# P_09__eMMC_QSPI.net
KiCad netlist of a schematic drawn in Altium Designer
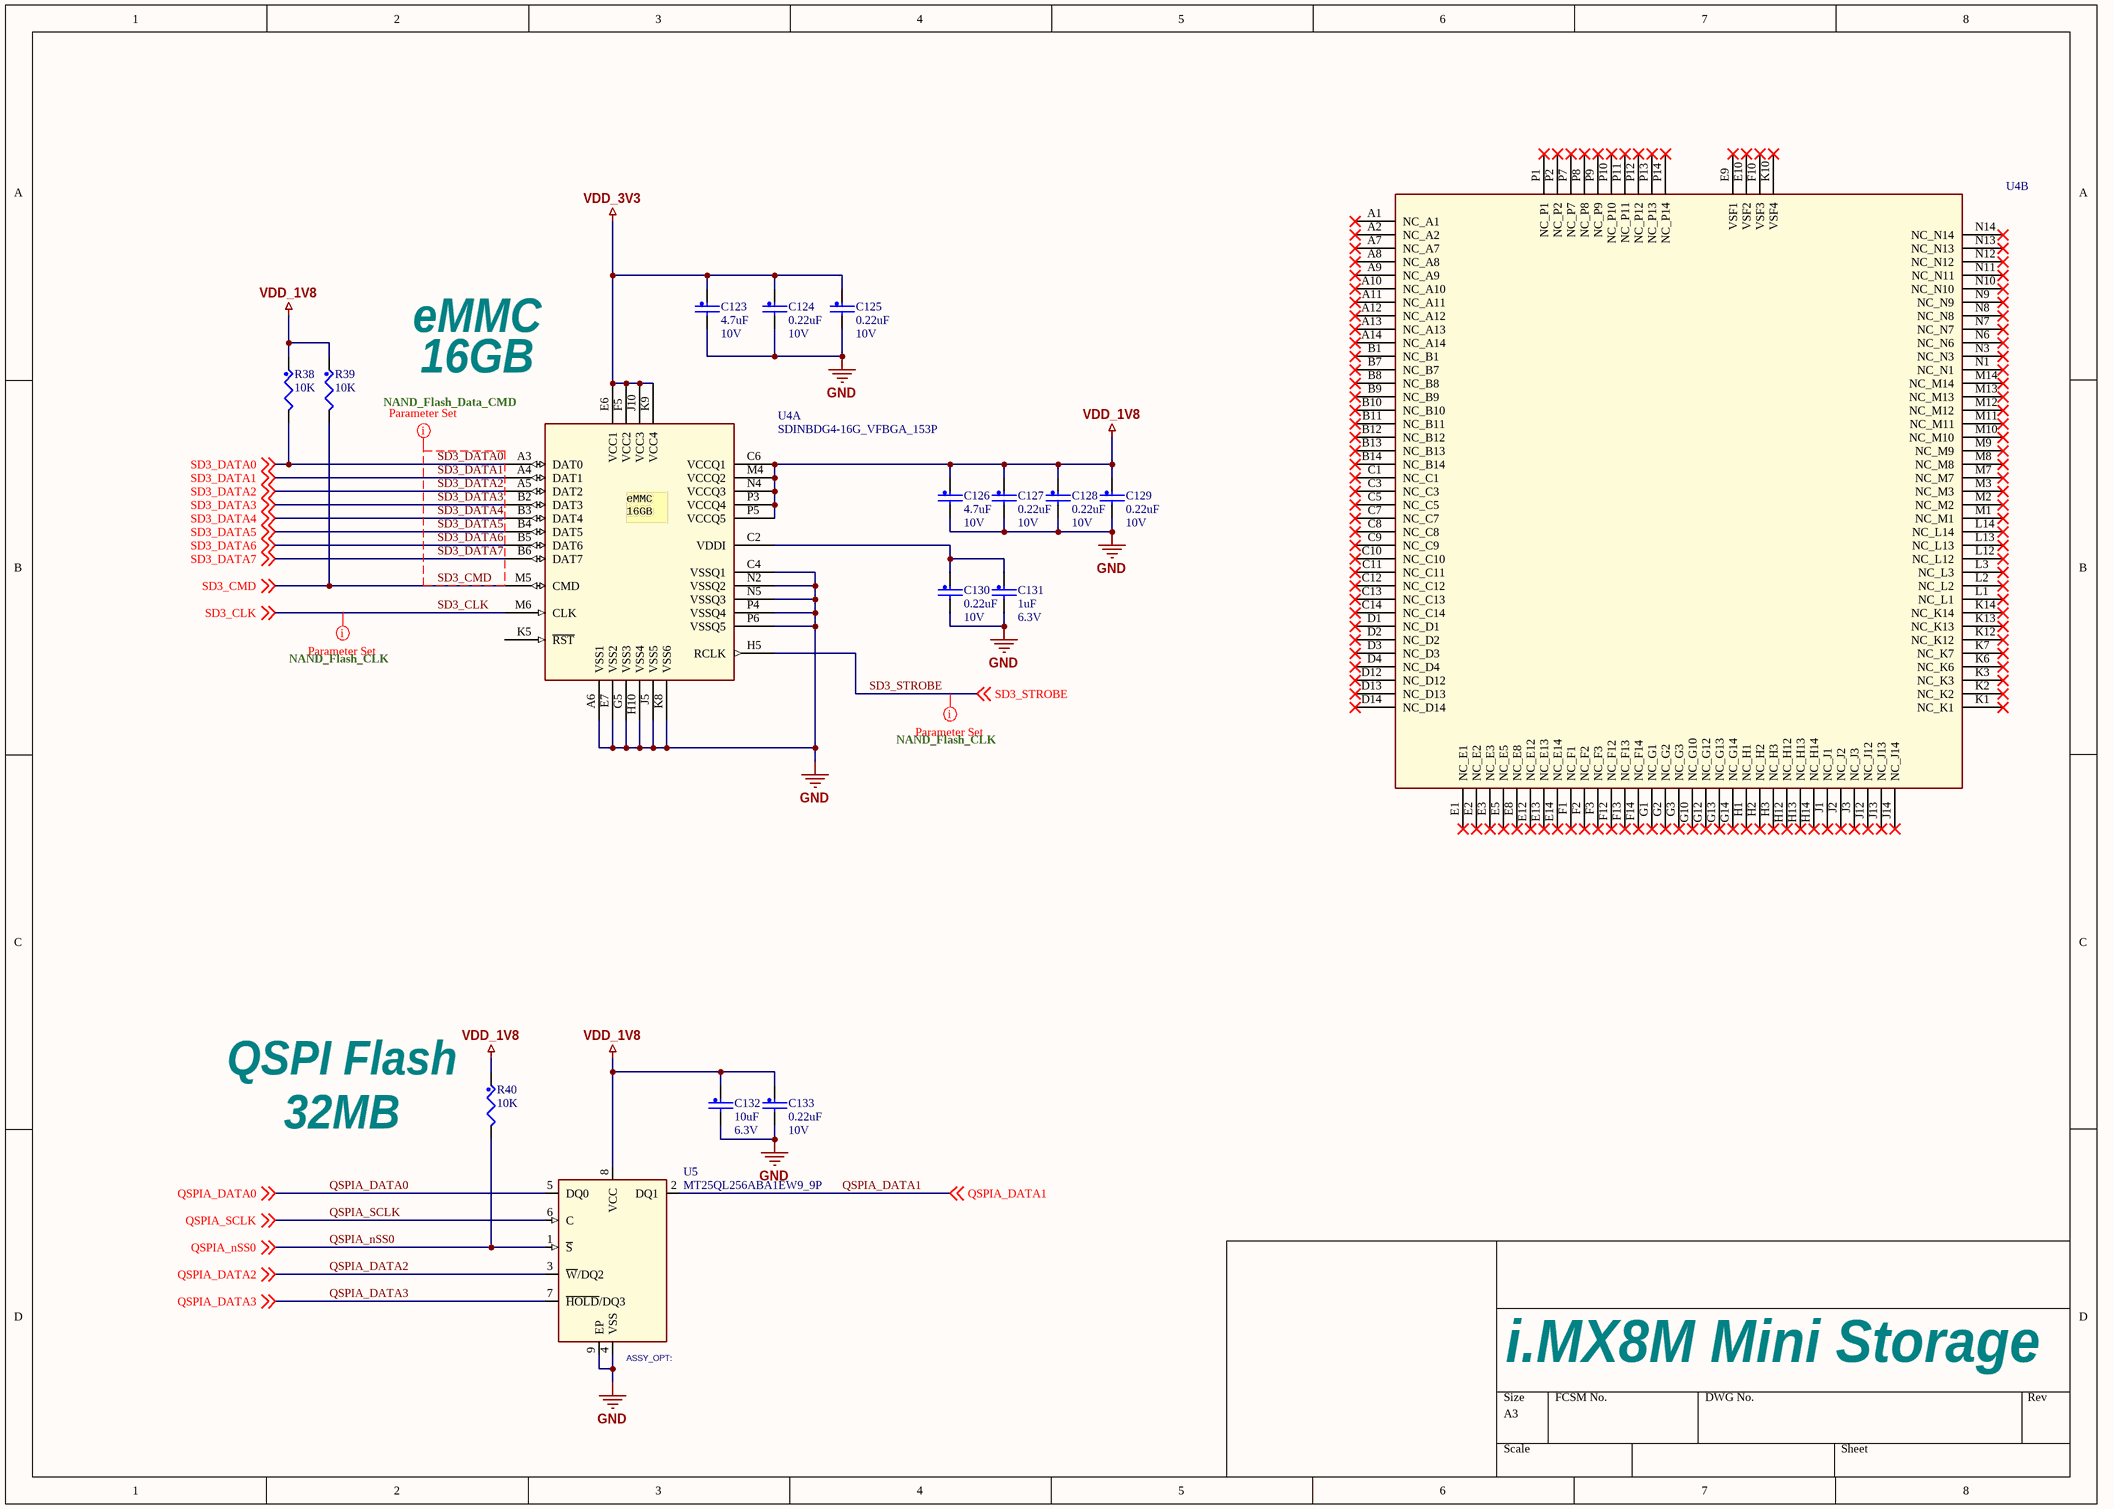
[diagram p0: P[09]_eMMC_QSPI.SchDoc]

(export (version "E")
  (design (tool "Eeschema 10.0.6"))
  (components
    (comp (ref "C123")
      (value "4.7uF")
      (footprint "0402_CC - C")
      (fields (field (name "VOLTAGE") "10V"))
      (libsource (lib "AA_iMX8_M_") (part "CAP_NP"))
    )
    (comp (ref "C124")
      (value "0.22uF")
      (footprint "0201_CC - C")
      (fields (field (name "VOLTAGE") "10V"))
      (libsource (lib "AA_iMX8_M_") (part "CAP_NP"))
    )
    (comp (ref "C125")
      (value "0.22uF")
      (footprint "0201_CC - C")
      (fields (field (name "VOLTAGE") "10V"))
      (libsource (lib "AA_iMX8_M_") (part "CAP_NP"))
    )
    (comp (ref "C126")
      (value "4.7uF")
      (footprint "0402_CC - C")
      (fields (field (name "VOLTAGE") "10V"))
      (libsource (lib "AA_iMX8_M_") (part "CAP_NP"))
    )
    (comp (ref "C127")
      (value "0.22uF")
      (footprint "0201_CC - C")
      (fields (field (name "VOLTAGE") "10V"))
      (libsource (lib "AA_iMX8_M_") (part "CAP_NP"))
    )
    (comp (ref "C128")
      (value "0.22uF")
      (footprint "0201_CC - C")
      (fields (field (name "VOLTAGE") "10V"))
      (libsource (lib "AA_iMX8_M_") (part "CAP_NP"))
    )
    (comp (ref "C129")
      (value "0.22uF")
      (footprint "0201_CC - C")
      (fields (field (name "VOLTAGE") "10V"))
      (libsource (lib "AA_iMX8_M_") (part "CAP_NP"))
    )
    (comp (ref "C130")
      (value "0.22uF")
      (footprint "0201_CC - C")
      (fields (field (name "VOLTAGE") "10V"))
      (libsource (lib "AA_iMX8_M_") (part "CAP_NP"))
    )
    (comp (ref "C131")
      (value "1uF")
      (footprint "0201_CC - C")
      (fields (field (name "VOLTAGE") "6.3V"))
      (libsource (lib "AA_iMX8_M_") (part "CAP_NP"))
    )
    (comp (ref "C132")
      (value "10uF")
      (footprint "0402_CC - C")
      (fields (field (name "VOLTAGE") "6.3V"))
      (libsource (lib "AA_iMX8_M_") (part "CAP_NP"))
    )
    (comp (ref "C133")
      (value "0.22uF")
      (footprint "0201_CC - C")
      (fields (field (name "VOLTAGE") "10V"))
      (libsource (lib "AA_iMX8_M_") (part "CAP_NP"))
    )
    (comp (ref "R38") (value "10K") (footprint "0201_CC") (libsource (lib "AA_iMX8_M_") (part "RES")))
    (comp (ref "R39") (value "10K") (footprint "0201_CC") (libsource (lib "AA_iMX8_M_") (part "RES")))
    (comp (ref "R40") (value "10K") (footprint "0402_CC") (libsource (lib "AA_iMX8_M_") (part "RES")))
    (comp (ref "U4")
      (value "SDINBDG4-16G_VFBGA_153P")
      (footprint "FBGA153_0P5_11P5X13")
      (libsource (lib "AA_iMX8_M_") (part "SDINBDG4-16G_VFBGA_153P"))
    )
    (comp (ref "U5")
      (value "MT25QL256ABA1EW9_9P")
      (footprint "DFN8_1P27_6X5MM_3P1")
      (libsource (lib "AA_iMX8_M_") (part "MT25QL256ABA1EW9_9P"))
    )
  )
  (nets
    (net (code "1") (name "GND") (class "Default")
      (node (ref "C123") (pin "2") (pinfunction "2_2") (pintype "passive"))
      (node (ref "C124") (pin "2") (pinfunction "2_2") (pintype "passive"))
      (node (ref "C125") (pin "2") (pinfunction "2_2") (pintype "passive"))
      (node (ref "C126") (pin "2") (pinfunction "2_2") (pintype "passive"))
      (node (ref "C127") (pin "2") (pinfunction "2_2") (pintype "passive"))
      (node (ref "C128") (pin "2") (pinfunction "2_2") (pintype "passive"))
      (node (ref "C129") (pin "2") (pinfunction "2_2") (pintype "passive"))
      (node (ref "C130") (pin "2") (pinfunction "2_2") (pintype "passive"))
      (node (ref "C131") (pin "2") (pinfunction "2_2") (pintype "passive"))
      (node (ref "C132") (pin "2") (pinfunction "2_2") (pintype "passive"))
      (node (ref "C133") (pin "2") (pinfunction "2_2") (pintype "passive"))
      (node (ref "U4") (pin "A6") (pinfunction "VSS1_A6") (pintype "power_in"))
      (node (ref "U4") (pin "C4") (pinfunction "VSSQ1_C4") (pintype "power_in"))
      (node (ref "U4") (pin "E7") (pinfunction "VSS2_E7") (pintype "power_in"))
      (node (ref "U4") (pin "G5") (pinfunction "VSS3_G5") (pintype "power_in"))
      (node (ref "U4") (pin "H10") (pinfunction "VSS4_H10") (pintype "power_in"))
      (node (ref "U4") (pin "J5") (pinfunction "VSS5_J5") (pintype "power_in"))
      (node (ref "U4") (pin "K8") (pinfunction "VSS6_K8") (pintype "power_in"))
      (node (ref "U4") (pin "N2") (pinfunction "VSSQ2_N2") (pintype "power_in"))
      (node (ref "U4") (pin "N5") (pinfunction "VSSQ3_N5") (pintype "power_in"))
      (node (ref "U4") (pin "P4") (pinfunction "VSSQ4_P4") (pintype "power_in"))
      (node (ref "U4") (pin "P6") (pinfunction "VSSQ5_P6") (pintype "power_in"))
      (node (ref "U5") (pin "4") (pinfunction "VSS_4") (pintype "power_in"))
      (node (ref "U5") (pin "9") (pinfunction "EP_9") (pintype "power_in"))
    )
    (net (code "2") (name "Net-(U4A-VDDI)") (class "Default")
      (node (ref "C130") (pin "1") (pinfunction "1_1") (pintype "passive"))
      (node (ref "C131") (pin "1") (pinfunction "1_1") (pintype "passive"))
      (node (ref "U4") (pin "C2") (pinfunction "VDDI_C2") (pintype "power_in"))
    )
    (net (code "3") (name "QSPIA_DATA0") (class "Default")
      (node (ref "U5") (pin "5") (pinfunction "DQ0_5") (pintype "bidirectional"))
    )
    (net (code "4") (name "QSPIA_DATA1") (class "Default")
      (node (ref "U5") (pin "2") (pinfunction "DQ1_2") (pintype "bidirectional"))
    )
    (net (code "5") (name "QSPIA_DATA2") (class "Default")
      (node (ref "U5") (pin "3") (pinfunction "~{W}/DQ2_3") (pintype "bidirectional"))
    )
    (net (code "6") (name "QSPIA_DATA3") (class "Default")
      (node (ref "U5") (pin "7") (pinfunction "~{HOLD}/DQ3_7") (pintype "bidirectional"))
    )
    (net (code "7") (name "QSPIA_SCLK") (class "Default")
      (node (ref "U5") (pin "6") (pinfunction "C_6") (pintype "input"))
    )
    (net (code "8") (name "QSPIA_nSS0") (class "Default")
      (node (ref "R40") (pin "2") (pinfunction "2_2") (pintype "passive"))
      (node (ref "U5") (pin "1") (pinfunction "~{S}_1") (pintype "input"))
    )
    (net (code "9") (name "SD3_CLK") (class "Default")
      (node (ref "U4") (pin "M6") (pinfunction "CLK_M6") (pintype "input"))
    )
    (net (code "10") (name "SD3_CMD") (class "Default")
      (node (ref "R39") (pin "2") (pinfunction "2_2") (pintype "passive"))
      (node (ref "U4") (pin "M5") (pinfunction "CMD_M5") (pintype "bidirectional"))
    )
    (net (code "11") (name "SD3_DATA0") (class "Default")
      (node (ref "R38") (pin "2") (pinfunction "2_2") (pintype "passive"))
      (node (ref "U4") (pin "A3") (pinfunction "DAT0_A3") (pintype "bidirectional"))
    )
    (net (code "12") (name "SD3_DATA1") (class "Default")
      (node (ref "U4") (pin "A4") (pinfunction "DAT1_A4") (pintype "bidirectional"))
    )
    (net (code "13") (name "SD3_DATA2") (class "Default")
      (node (ref "U4") (pin "A5") (pinfunction "DAT2_A5") (pintype "bidirectional"))
    )
    (net (code "14") (name "SD3_DATA3") (class "Default")
      (node (ref "U4") (pin "B2") (pinfunction "DAT3_B2") (pintype "bidirectional"))
    )
    (net (code "15") (name "SD3_DATA4") (class "Default")
      (node (ref "U4") (pin "B3") (pinfunction "DAT4_B3") (pintype "bidirectional"))
    )
    (net (code "16") (name "SD3_DATA5") (class "Default")
      (node (ref "U4") (pin "B4") (pinfunction "DAT5_B4") (pintype "bidirectional"))
    )
    (net (code "17") (name "SD3_DATA6") (class "Default")
      (node (ref "U4") (pin "B5") (pinfunction "DAT6_B5") (pintype "bidirectional"))
    )
    (net (code "18") (name "SD3_DATA7") (class "Default")
      (node (ref "U4") (pin "B6") (pinfunction "DAT7_B6") (pintype "bidirectional"))
    )
    (net (code "19") (name "SD3_STROBE") (class "Default")
      (node (ref "U4") (pin "H5") (pinfunction "RCLK_H5") (pintype "output"))
    )
    (net (code "20") (name "VDD_1V8") (class "Default")
      (node (ref "C126") (pin "1") (pinfunction "1_1") (pintype "passive"))
      (node (ref "C127") (pin "1") (pinfunction "1_1") (pintype "passive"))
      (node (ref "C128") (pin "1") (pinfunction "1_1") (pintype "passive"))
      (node (ref "C129") (pin "1") (pinfunction "1_1") (pintype "passive"))
      (node (ref "C132") (pin "1") (pinfunction "1_1") (pintype "passive"))
      (node (ref "C133") (pin "1") (pinfunction "1_1") (pintype "passive"))
      (node (ref "R38") (pin "1") (pinfunction "1_1") (pintype "passive"))
      (node (ref "R39") (pin "1") (pinfunction "1_1") (pintype "passive"))
      (node (ref "R40") (pin "1") (pinfunction "1_1") (pintype "passive"))
      (node (ref "U4") (pin "C6") (pinfunction "VCCQ1_C6") (pintype "power_in"))
      (node (ref "U4") (pin "M4") (pinfunction "VCCQ2_M4") (pintype "power_in"))
      (node (ref "U4") (pin "N4") (pinfunction "VCCQ3_N4") (pintype "power_in"))
      (node (ref "U4") (pin "P3") (pinfunction "VCCQ4_P3") (pintype "power_in"))
      (node (ref "U4") (pin "P5") (pinfunction "VCCQ5_P5") (pintype "power_in"))
      (node (ref "U5") (pin "8") (pinfunction "VCC_8") (pintype "power_in"))
    )
    (net (code "21") (name "VDD_3V3") (class "Default")
      (node (ref "C123") (pin "1") (pinfunction "1_1") (pintype "passive"))
      (node (ref "C124") (pin "1") (pinfunction "1_1") (pintype "passive"))
      (node (ref "C125") (pin "1") (pinfunction "1_1") (pintype "passive"))
      (node (ref "U4") (pin "E6") (pinfunction "VCC1_E6") (pintype "power_in"))
      (node (ref "U4") (pin "F5") (pinfunction "VCC2_F5") (pintype "power_in"))
      (node (ref "U4") (pin "J10") (pinfunction "VCC3_J10") (pintype "power_in"))
      (node (ref "U4") (pin "K9") (pinfunction "VCC4_K9") (pintype "power_in"))
    )
    (net (code "22") (name "unconnected-(U4A-~{RST}-PadK5)") (class "Default")
      (node (ref "U4") (pin "K5") (pinfunction "~{RST}_K5") (pintype "input"))
    )
    (net (code "23") (name "unconnected-(U4B-NC_A1-PadA1)") (class "Default")
      (node (ref "U4") (pin "A1") (pinfunction "NC_A1_A1") (pintype "passive+no_connect"))
    )
    (net (code "24") (name "unconnected-(U4B-NC_A2-PadA2)") (class "Default")
      (node (ref "U4") (pin "A2") (pinfunction "NC_A2_A2") (pintype "passive+no_connect"))
    )
    (net (code "25") (name "unconnected-(U4B-NC_A7-PadA7)") (class "Default")
      (node (ref "U4") (pin "A7") (pinfunction "NC_A7_A7") (pintype "passive+no_connect"))
    )
    (net (code "26") (name "unconnected-(U4B-NC_A8-PadA8)") (class "Default")
      (node (ref "U4") (pin "A8") (pinfunction "NC_A8_A8") (pintype "passive+no_connect"))
    )
    (net (code "27") (name "unconnected-(U4B-NC_A9-PadA9)") (class "Default")
      (node (ref "U4") (pin "A9") (pinfunction "NC_A9_A9") (pintype "passive+no_connect"))
    )
    (net (code "28") (name "unconnected-(U4B-NC_A10-PadA10)") (class "Default")
      (node (ref "U4") (pin "A10") (pinfunction "NC_A10_A10") (pintype "passive+no_connect"))
    )
    (net (code "29") (name "unconnected-(U4B-NC_A11-PadA11)") (class "Default")
      (node (ref "U4") (pin "A11") (pinfunction "NC_A11_A11") (pintype "passive+no_connect"))
    )
    (net (code "30") (name "unconnected-(U4B-NC_A12-PadA12)") (class "Default")
      (node (ref "U4") (pin "A12") (pinfunction "NC_A12_A12") (pintype "passive+no_connect"))
    )
    (net (code "31") (name "unconnected-(U4B-NC_A13-PadA13)") (class "Default")
      (node (ref "U4") (pin "A13") (pinfunction "NC_A13_A13") (pintype "passive+no_connect"))
    )
    (net (code "32") (name "unconnected-(U4B-NC_A14-PadA14)") (class "Default")
      (node (ref "U4") (pin "A14") (pinfunction "NC_A14_A14") (pintype "passive+no_connect"))
    )
    (net (code "33") (name "unconnected-(U4B-NC_B1-PadB1)") (class "Default")
      (node (ref "U4") (pin "B1") (pinfunction "NC_B1_B1") (pintype "passive+no_connect"))
    )
    (net (code "34") (name "unconnected-(U4B-NC_B7-PadB7)") (class "Default")
      (node (ref "U4") (pin "B7") (pinfunction "NC_B7_B7") (pintype "passive+no_connect"))
    )
    (net (code "35") (name "unconnected-(U4B-NC_B8-PadB8)") (class "Default")
      (node (ref "U4") (pin "B8") (pinfunction "NC_B8_B8") (pintype "passive+no_connect"))
    )
    (net (code "36") (name "unconnected-(U4B-NC_B9-PadB9)") (class "Default")
      (node (ref "U4") (pin "B9") (pinfunction "NC_B9_B9") (pintype "passive+no_connect"))
    )
    (net (code "37") (name "unconnected-(U4B-NC_B10-PadB10)") (class "Default")
      (node (ref "U4") (pin "B10") (pinfunction "NC_B10_B10") (pintype "passive+no_connect"))
    )
    (net (code "38") (name "unconnected-(U4B-NC_B11-PadB11)") (class "Default")
      (node (ref "U4") (pin "B11") (pinfunction "NC_B11_B11") (pintype "passive+no_connect"))
    )
    (net (code "39") (name "unconnected-(U4B-NC_B12-PadB12)") (class "Default")
      (node (ref "U4") (pin "B12") (pinfunction "NC_B12_B12") (pintype "passive+no_connect"))
    )
    (net (code "40") (name "unconnected-(U4B-NC_B13-PadB13)") (class "Default")
      (node (ref "U4") (pin "B13") (pinfunction "NC_B13_B13") (pintype "passive+no_connect"))
    )
    (net (code "41") (name "unconnected-(U4B-NC_B14-PadB14)") (class "Default")
      (node (ref "U4") (pin "B14") (pinfunction "NC_B14_B14") (pintype "passive+no_connect"))
    )
    (net (code "42") (name "unconnected-(U4B-NC_C1-PadC1)") (class "Default")
      (node (ref "U4") (pin "C1") (pinfunction "NC_C1_C1") (pintype "passive+no_connect"))
    )
    (net (code "43") (name "unconnected-(U4B-NC_C3-PadC3)") (class "Default")
      (node (ref "U4") (pin "C3") (pinfunction "NC_C3_C3") (pintype "passive+no_connect"))
    )
    (net (code "44") (name "unconnected-(U4B-NC_C5-PadC5)") (class "Default")
      (node (ref "U4") (pin "C5") (pinfunction "NC_C5_C5") (pintype "passive+no_connect"))
    )
    (net (code "45") (name "unconnected-(U4B-NC_C7-PadC7)") (class "Default")
      (node (ref "U4") (pin "C7") (pinfunction "NC_C7_C7") (pintype "passive+no_connect"))
    )
    (net (code "46") (name "unconnected-(U4B-NC_C8-PadC8)") (class "Default")
      (node (ref "U4") (pin "C8") (pinfunction "NC_C8_C8") (pintype "passive+no_connect"))
    )
    (net (code "47") (name "unconnected-(U4B-NC_C9-PadC9)") (class "Default")
      (node (ref "U4") (pin "C9") (pinfunction "NC_C9_C9") (pintype "passive+no_connect"))
    )
    (net (code "48") (name "unconnected-(U4B-NC_C10-PadC10)") (class "Default")
      (node (ref "U4") (pin "C10") (pinfunction "NC_C10_C10") (pintype "passive+no_connect"))
    )
    (net (code "49") (name "unconnected-(U4B-NC_C11-PadC11)") (class "Default")
      (node (ref "U4") (pin "C11") (pinfunction "NC_C11_C11") (pintype "passive+no_connect"))
    )
    (net (code "50") (name "unconnected-(U4B-NC_C12-PadC12)") (class "Default")
      (node (ref "U4") (pin "C12") (pinfunction "NC_C12_C12") (pintype "passive+no_connect"))
    )
    (net (code "51") (name "unconnected-(U4B-NC_C13-PadC13)") (class "Default")
      (node (ref "U4") (pin "C13") (pinfunction "NC_C13_C13") (pintype "passive+no_connect"))
    )
    (net (code "52") (name "unconnected-(U4B-NC_C14-PadC14)") (class "Default")
      (node (ref "U4") (pin "C14") (pinfunction "NC_C14_C14") (pintype "passive+no_connect"))
    )
    (net (code "53") (name "unconnected-(U4B-NC_D1-PadD1)") (class "Default")
      (node (ref "U4") (pin "D1") (pinfunction "NC_D1_D1") (pintype "passive+no_connect"))
    )
    (net (code "54") (name "unconnected-(U4B-NC_D2-PadD2)") (class "Default")
      (node (ref "U4") (pin "D2") (pinfunction "NC_D2_D2") (pintype "passive+no_connect"))
    )
    (net (code "55") (name "unconnected-(U4B-NC_D3-PadD3)") (class "Default")
      (node (ref "U4") (pin "D3") (pinfunction "NC_D3_D3") (pintype "passive+no_connect"))
    )
    (net (code "56") (name "unconnected-(U4B-NC_D4-PadD4)") (class "Default")
      (node (ref "U4") (pin "D4") (pinfunction "NC_D4_D4") (pintype "passive+no_connect"))
    )
    (net (code "57") (name "unconnected-(U4B-NC_D12-PadD12)") (class "Default")
      (node (ref "U4") (pin "D12") (pinfunction "NC_D12_D12") (pintype "passive+no_connect"))
    )
    (net (code "58") (name "unconnected-(U4B-NC_D13-PadD13)") (class "Default")
      (node (ref "U4") (pin "D13") (pinfunction "NC_D13_D13") (pintype "passive+no_connect"))
    )
    (net (code "59") (name "unconnected-(U4B-NC_D14-PadD14)") (class "Default")
      (node (ref "U4") (pin "D14") (pinfunction "NC_D14_D14") (pintype "passive+no_connect"))
    )
    (net (code "60") (name "unconnected-(U4B-NC_E1-PadE1)") (class "Default")
      (node (ref "U4") (pin "E1") (pinfunction "NC_E1_E1") (pintype "passive+no_connect"))
    )
    (net (code "61") (name "unconnected-(U4B-NC_E2-PadE2)") (class "Default")
      (node (ref "U4") (pin "E2") (pinfunction "NC_E2_E2") (pintype "passive+no_connect"))
    )
    (net (code "62") (name "unconnected-(U4B-NC_E3-PadE3)") (class "Default")
      (node (ref "U4") (pin "E3") (pinfunction "NC_E3_E3") (pintype "passive+no_connect"))
    )
    (net (code "63") (name "unconnected-(U4B-NC_E5-PadE5)") (class "Default")
      (node (ref "U4") (pin "E5") (pinfunction "NC_E5_E5") (pintype "passive+no_connect"))
    )
    (net (code "64") (name "unconnected-(U4B-NC_E8-PadE8)") (class "Default")
      (node (ref "U4") (pin "E8") (pinfunction "NC_E8_E8") (pintype "passive+no_connect"))
    )
    (net (code "65") (name "unconnected-(U4B-NC_E12-PadE12)") (class "Default")
      (node (ref "U4") (pin "E12") (pinfunction "NC_E12_E12") (pintype "passive+no_connect"))
    )
    (net (code "66") (name "unconnected-(U4B-NC_E13-PadE13)") (class "Default")
      (node (ref "U4") (pin "E13") (pinfunction "NC_E13_E13") (pintype "passive+no_connect"))
    )
    (net (code "67") (name "unconnected-(U4B-NC_E14-PadE14)") (class "Default")
      (node (ref "U4") (pin "E14") (pinfunction "NC_E14_E14") (pintype "passive+no_connect"))
    )
    (net (code "68") (name "unconnected-(U4B-NC_F1-PadF1)") (class "Default")
      (node (ref "U4") (pin "F1") (pinfunction "NC_F1_F1") (pintype "passive+no_connect"))
    )
    (net (code "69") (name "unconnected-(U4B-NC_F2-PadF2)") (class "Default")
      (node (ref "U4") (pin "F2") (pinfunction "NC_F2_F2") (pintype "passive+no_connect"))
    )
    (net (code "70") (name "unconnected-(U4B-NC_F3-PadF3)") (class "Default")
      (node (ref "U4") (pin "F3") (pinfunction "NC_F3_F3") (pintype "passive+no_connect"))
    )
    (net (code "71") (name "unconnected-(U4B-NC_F12-PadF12)") (class "Default")
      (node (ref "U4") (pin "F12") (pinfunction "NC_F12_F12") (pintype "passive+no_connect"))
    )
    (net (code "72") (name "unconnected-(U4B-NC_F13-PadF13)") (class "Default")
      (node (ref "U4") (pin "F13") (pinfunction "NC_F13_F13") (pintype "passive+no_connect"))
    )
    (net (code "73") (name "unconnected-(U4B-NC_F14-PadF14)") (class "Default")
      (node (ref "U4") (pin "F14") (pinfunction "NC_F14_F14") (pintype "passive+no_connect"))
    )
    (net (code "74") (name "unconnected-(U4B-NC_G1-PadG1)") (class "Default")
      (node (ref "U4") (pin "G1") (pinfunction "NC_G1_G1") (pintype "passive+no_connect"))
    )
    (net (code "75") (name "unconnected-(U4B-NC_G2-PadG2)") (class "Default")
      (node (ref "U4") (pin "G2") (pinfunction "NC_G2_G2") (pintype "passive+no_connect"))
    )
    (net (code "76") (name "unconnected-(U4B-NC_G3-PadG3)") (class "Default")
      (node (ref "U4") (pin "G3") (pinfunction "NC_G3_G3") (pintype "passive+no_connect"))
    )
    (net (code "77") (name "unconnected-(U4B-NC_G10-PadG10)") (class "Default")
      (node (ref "U4") (pin "G10") (pinfunction "NC_G10_G10") (pintype "passive+no_connect"))
    )
    (net (code "78") (name "unconnected-(U4B-NC_G12-PadG12)") (class "Default")
      (node (ref "U4") (pin "G12") (pinfunction "NC_G12_G12") (pintype "passive+no_connect"))
    )
    (net (code "79") (name "unconnected-(U4B-NC_G13-PadG13)") (class "Default")
      (node (ref "U4") (pin "G13") (pinfunction "NC_G13_G13") (pintype "passive+no_connect"))
    )
    (net (code "80") (name "unconnected-(U4B-NC_G14-PadG14)") (class "Default")
      (node (ref "U4") (pin "G14") (pinfunction "NC_G14_G14") (pintype "passive+no_connect"))
    )
    (net (code "81") (name "unconnected-(U4B-NC_H1-PadH1)") (class "Default")
      (node (ref "U4") (pin "H1") (pinfunction "NC_H1_H1") (pintype "passive+no_connect"))
    )
    (net (code "82") (name "unconnected-(U4B-NC_H2-PadH2)") (class "Default")
      (node (ref "U4") (pin "H2") (pinfunction "NC_H2_H2") (pintype "passive+no_connect"))
    )
    (net (code "83") (name "unconnected-(U4B-NC_H3-PadH3)") (class "Default")
      (node (ref "U4") (pin "H3") (pinfunction "NC_H3_H3") (pintype "passive+no_connect"))
    )
    (net (code "84") (name "unconnected-(U4B-NC_H12-PadH12)") (class "Default")
      (node (ref "U4") (pin "H12") (pinfunction "NC_H12_H12") (pintype "passive+no_connect"))
    )
    (net (code "85") (name "unconnected-(U4B-NC_H13-PadH13)") (class "Default")
      (node (ref "U4") (pin "H13") (pinfunction "NC_H13_H13") (pintype "passive+no_connect"))
    )
    (net (code "86") (name "unconnected-(U4B-NC_H14-PadH14)") (class "Default")
      (node (ref "U4") (pin "H14") (pinfunction "NC_H14_H14") (pintype "passive+no_connect"))
    )
    (net (code "87") (name "unconnected-(U4B-NC_J1-PadJ1)") (class "Default")
      (node (ref "U4") (pin "J1") (pinfunction "NC_J1_J1") (pintype "passive+no_connect"))
    )
    (net (code "88") (name "unconnected-(U4B-NC_J2-PadJ2)") (class "Default")
      (node (ref "U4") (pin "J2") (pinfunction "NC_J2_J2") (pintype "passive+no_connect"))
    )
    (net (code "89") (name "unconnected-(U4B-NC_J3-PadJ3)") (class "Default")
      (node (ref "U4") (pin "J3") (pinfunction "NC_J3_J3") (pintype "passive+no_connect"))
    )
    (net (code "90") (name "unconnected-(U4B-NC_J12-PadJ12)") (class "Default")
      (node (ref "U4") (pin "J12") (pinfunction "NC_J12_J12") (pintype "passive+no_connect"))
    )
    (net (code "91") (name "unconnected-(U4B-NC_J13-PadJ13)") (class "Default")
      (node (ref "U4") (pin "J13") (pinfunction "NC_J13_J13") (pintype "passive+no_connect"))
    )
    (net (code "92") (name "unconnected-(U4B-NC_J14-PadJ14)") (class "Default")
      (node (ref "U4") (pin "J14") (pinfunction "NC_J14_J14") (pintype "passive+no_connect"))
    )
    (net (code "93") (name "unconnected-(U4B-NC_K1-PadK1)") (class "Default")
      (node (ref "U4") (pin "K1") (pinfunction "NC_K1_K1") (pintype "passive+no_connect"))
    )
    (net (code "94") (name "unconnected-(U4B-NC_K2-PadK2)") (class "Default")
      (node (ref "U4") (pin "K2") (pinfunction "NC_K2_K2") (pintype "passive+no_connect"))
    )
    (net (code "95") (name "unconnected-(U4B-NC_K3-PadK3)") (class "Default")
      (node (ref "U4") (pin "K3") (pinfunction "NC_K3_K3") (pintype "passive+no_connect"))
    )
    (net (code "96") (name "unconnected-(U4B-NC_K6-PadK6)") (class "Default")
      (node (ref "U4") (pin "K6") (pinfunction "NC_K6_K6") (pintype "passive+no_connect"))
    )
    (net (code "97") (name "unconnected-(U4B-NC_K7-PadK7)") (class "Default")
      (node (ref "U4") (pin "K7") (pinfunction "NC_K7_K7") (pintype "passive+no_connect"))
    )
    (net (code "98") (name "unconnected-(U4B-NC_K12-PadK12)") (class "Default")
      (node (ref "U4") (pin "K12") (pinfunction "NC_K12_K12") (pintype "passive+no_connect"))
    )
    (net (code "99") (name "unconnected-(U4B-NC_K13-PadK13)") (class "Default")
      (node (ref "U4") (pin "K13") (pinfunction "NC_K13_K13") (pintype "passive+no_connect"))
    )
    (net (code "100") (name "unconnected-(U4B-NC_K14-PadK14)") (class "Default")
      (node (ref "U4") (pin "K14") (pinfunction "NC_K14_K14") (pintype "passive+no_connect"))
    )
    (net (code "101") (name "unconnected-(U4B-NC_L1-PadL1)") (class "Default")
      (node (ref "U4") (pin "L1") (pinfunction "NC_L1_L1") (pintype "passive+no_connect"))
    )
    (net (code "102") (name "unconnected-(U4B-NC_L2-PadL2)") (class "Default")
      (node (ref "U4") (pin "L2") (pinfunction "NC_L2_L2") (pintype "passive+no_connect"))
    )
    (net (code "103") (name "unconnected-(U4B-NC_L3-PadL3)") (class "Default")
      (node (ref "U4") (pin "L3") (pinfunction "NC_L3_L3") (pintype "passive+no_connect"))
    )
    (net (code "104") (name "unconnected-(U4B-NC_L12-PadL12)") (class "Default")
      (node (ref "U4") (pin "L12") (pinfunction "NC_L12_L12") (pintype "passive+no_connect"))
    )
    (net (code "105") (name "unconnected-(U4B-NC_L13-PadL13)") (class "Default")
      (node (ref "U4") (pin "L13") (pinfunction "NC_L13_L13") (pintype "passive+no_connect"))
    )
    (net (code "106") (name "unconnected-(U4B-NC_L14-PadL14)") (class "Default")
      (node (ref "U4") (pin "L14") (pinfunction "NC_L14_L14") (pintype "passive+no_connect"))
    )
    (net (code "107") (name "unconnected-(U4B-NC_M1-PadM1)") (class "Default")
      (node (ref "U4") (pin "M1") (pinfunction "NC_M1_M1") (pintype "passive+no_connect"))
    )
    (net (code "108") (name "unconnected-(U4B-NC_M2-PadM2)") (class "Default")
      (node (ref "U4") (pin "M2") (pinfunction "NC_M2_M2") (pintype "passive+no_connect"))
    )
    (net (code "109") (name "unconnected-(U4B-NC_M3-PadM3)") (class "Default")
      (node (ref "U4") (pin "M3") (pinfunction "NC_M3_M3") (pintype "passive+no_connect"))
    )
    (net (code "110") (name "unconnected-(U4B-NC_M7-PadM7)") (class "Default")
      (node (ref "U4") (pin "M7") (pinfunction "NC_M7_M7") (pintype "passive+no_connect"))
    )
    (net (code "111") (name "unconnected-(U4B-NC_M8-PadM8)") (class "Default")
      (node (ref "U4") (pin "M8") (pinfunction "NC_M8_M8") (pintype "passive+no_connect"))
    )
    (net (code "112") (name "unconnected-(U4B-NC_M9-PadM9)") (class "Default")
      (node (ref "U4") (pin "M9") (pinfunction "NC_M9_M9") (pintype "passive+no_connect"))
    )
    (net (code "113") (name "unconnected-(U4B-NC_M10-PadM10)") (class "Default")
      (node (ref "U4") (pin "M10") (pinfunction "NC_M10_M10") (pintype "passive+no_connect"))
    )
    (net (code "114") (name "unconnected-(U4B-NC_M11-PadM11)") (class "Default")
      (node (ref "U4") (pin "M11") (pinfunction "NC_M11_M11") (pintype "passive+no_connect"))
    )
    (net (code "115") (name "unconnected-(U4B-NC_M12-PadM12)") (class "Default")
      (node (ref "U4") (pin "M12") (pinfunction "NC_M12_M12") (pintype "passive+no_connect"))
    )
    (net (code "116") (name "unconnected-(U4B-NC_M13-PadM13)") (class "Default")
      (node (ref "U4") (pin "M13") (pinfunction "NC_M13_M13") (pintype "passive+no_connect"))
    )
    (net (code "117") (name "unconnected-(U4B-NC_M14-PadM14)") (class "Default")
      (node (ref "U4") (pin "M14") (pinfunction "NC_M14_M14") (pintype "passive+no_connect"))
    )
    (net (code "118") (name "unconnected-(U4B-NC_N1-PadN1)") (class "Default")
      (node (ref "U4") (pin "N1") (pinfunction "NC_N1_N1") (pintype "passive+no_connect"))
    )
    (net (code "119") (name "unconnected-(U4B-NC_N3-PadN3)") (class "Default")
      (node (ref "U4") (pin "N3") (pinfunction "NC_N3_N3") (pintype "passive+no_connect"))
    )
    (net (code "120") (name "unconnected-(U4B-NC_N6-PadN6)") (class "Default")
      (node (ref "U4") (pin "N6") (pinfunction "NC_N6_N6") (pintype "passive+no_connect"))
    )
    (net (code "121") (name "unconnected-(U4B-NC_N7-PadN7)") (class "Default")
      (node (ref "U4") (pin "N7") (pinfunction "NC_N7_N7") (pintype "passive+no_connect"))
    )
    (net (code "122") (name "unconnected-(U4B-NC_N8-PadN8)") (class "Default")
      (node (ref "U4") (pin "N8") (pinfunction "NC_N8_N8") (pintype "passive+no_connect"))
    )
    (net (code "123") (name "unconnected-(U4B-NC_N9-PadN9)") (class "Default")
      (node (ref "U4") (pin "N9") (pinfunction "NC_N9_N9") (pintype "passive+no_connect"))
    )
    (net (code "124") (name "unconnected-(U4B-NC_N10-PadN10)") (class "Default")
      (node (ref "U4") (pin "N10") (pinfunction "NC_N10_N10") (pintype "passive+no_connect"))
    )
    (net (code "125") (name "unconnected-(U4B-NC_N11-PadN11)") (class "Default")
      (node (ref "U4") (pin "N11") (pinfunction "NC_N11_N11") (pintype "passive+no_connect"))
    )
    (net (code "126") (name "unconnected-(U4B-NC_N12-PadN12)") (class "Default")
      (node (ref "U4") (pin "N12") (pinfunction "NC_N12_N12") (pintype "passive+no_connect"))
    )
    (net (code "127") (name "unconnected-(U4B-NC_N13-PadN13)") (class "Default")
      (node (ref "U4") (pin "N13") (pinfunction "NC_N13_N13") (pintype "passive+no_connect"))
    )
    (net (code "128") (name "unconnected-(U4B-NC_N14-PadN14)") (class "Default")
      (node (ref "U4") (pin "N14") (pinfunction "NC_N14_N14") (pintype "passive+no_connect"))
    )
    (net (code "129") (name "unconnected-(U4B-NC_P1-PadP1)") (class "Default")
      (node (ref "U4") (pin "P1") (pinfunction "NC_P1_P1") (pintype "passive+no_connect"))
    )
    (net (code "130") (name "unconnected-(U4B-NC_P2-PadP2)") (class "Default")
      (node (ref "U4") (pin "P2") (pinfunction "NC_P2_P2") (pintype "passive+no_connect"))
    )
    (net (code "131") (name "unconnected-(U4B-NC_P7-PadP7)") (class "Default")
      (node (ref "U4") (pin "P7") (pinfunction "NC_P7_P7") (pintype "passive+no_connect"))
    )
    (net (code "132") (name "unconnected-(U4B-NC_P8-PadP8)") (class "Default")
      (node (ref "U4") (pin "P8") (pinfunction "NC_P8_P8") (pintype "passive+no_connect"))
    )
    (net (code "133") (name "unconnected-(U4B-NC_P9-PadP9)") (class "Default")
      (node (ref "U4") (pin "P9") (pinfunction "NC_P9_P9") (pintype "passive+no_connect"))
    )
    (net (code "134") (name "unconnected-(U4B-NC_P10-PadP10)") (class "Default")
      (node (ref "U4") (pin "P10") (pinfunction "NC_P10_P10") (pintype "passive+no_connect"))
    )
    (net (code "135") (name "unconnected-(U4B-NC_P11-PadP11)") (class "Default")
      (node (ref "U4") (pin "P11") (pinfunction "NC_P11_P11") (pintype "passive+no_connect"))
    )
    (net (code "136") (name "unconnected-(U4B-NC_P12-PadP12)") (class "Default")
      (node (ref "U4") (pin "P12") (pinfunction "NC_P12_P12") (pintype "passive+no_connect"))
    )
    (net (code "137") (name "unconnected-(U4B-NC_P13-PadP13)") (class "Default")
      (node (ref "U4") (pin "P13") (pinfunction "NC_P13_P13") (pintype "passive+no_connect"))
    )
    (net (code "138") (name "unconnected-(U4B-NC_P14-PadP14)") (class "Default")
      (node (ref "U4") (pin "P14") (pinfunction "NC_P14_P14") (pintype "passive+no_connect"))
    )
    (net (code "139") (name "unconnected-(U4B-VSF1-PadE9)") (class "Default")
      (node (ref "U4") (pin "E9") (pinfunction "VSF1_E9") (pintype "passive+no_connect"))
    )
    (net (code "140") (name "unconnected-(U4B-VSF2-PadE10)") (class "Default")
      (node (ref "U4") (pin "E10") (pinfunction "VSF2_E10") (pintype "passive+no_connect"))
    )
    (net (code "141") (name "unconnected-(U4B-VSF3-PadF10)") (class "Default")
      (node (ref "U4") (pin "F10") (pinfunction "VSF3_F10") (pintype "passive+no_connect"))
    )
    (net (code "142") (name "unconnected-(U4B-VSF4-PadK10)") (class "Default")
      (node (ref "U4") (pin "K10") (pinfunction "VSF4_K10") (pintype "passive+no_connect"))
    )
  )
)
